# Sheet1.net
KiCad netlist of a schematic drawn in Altium Designer
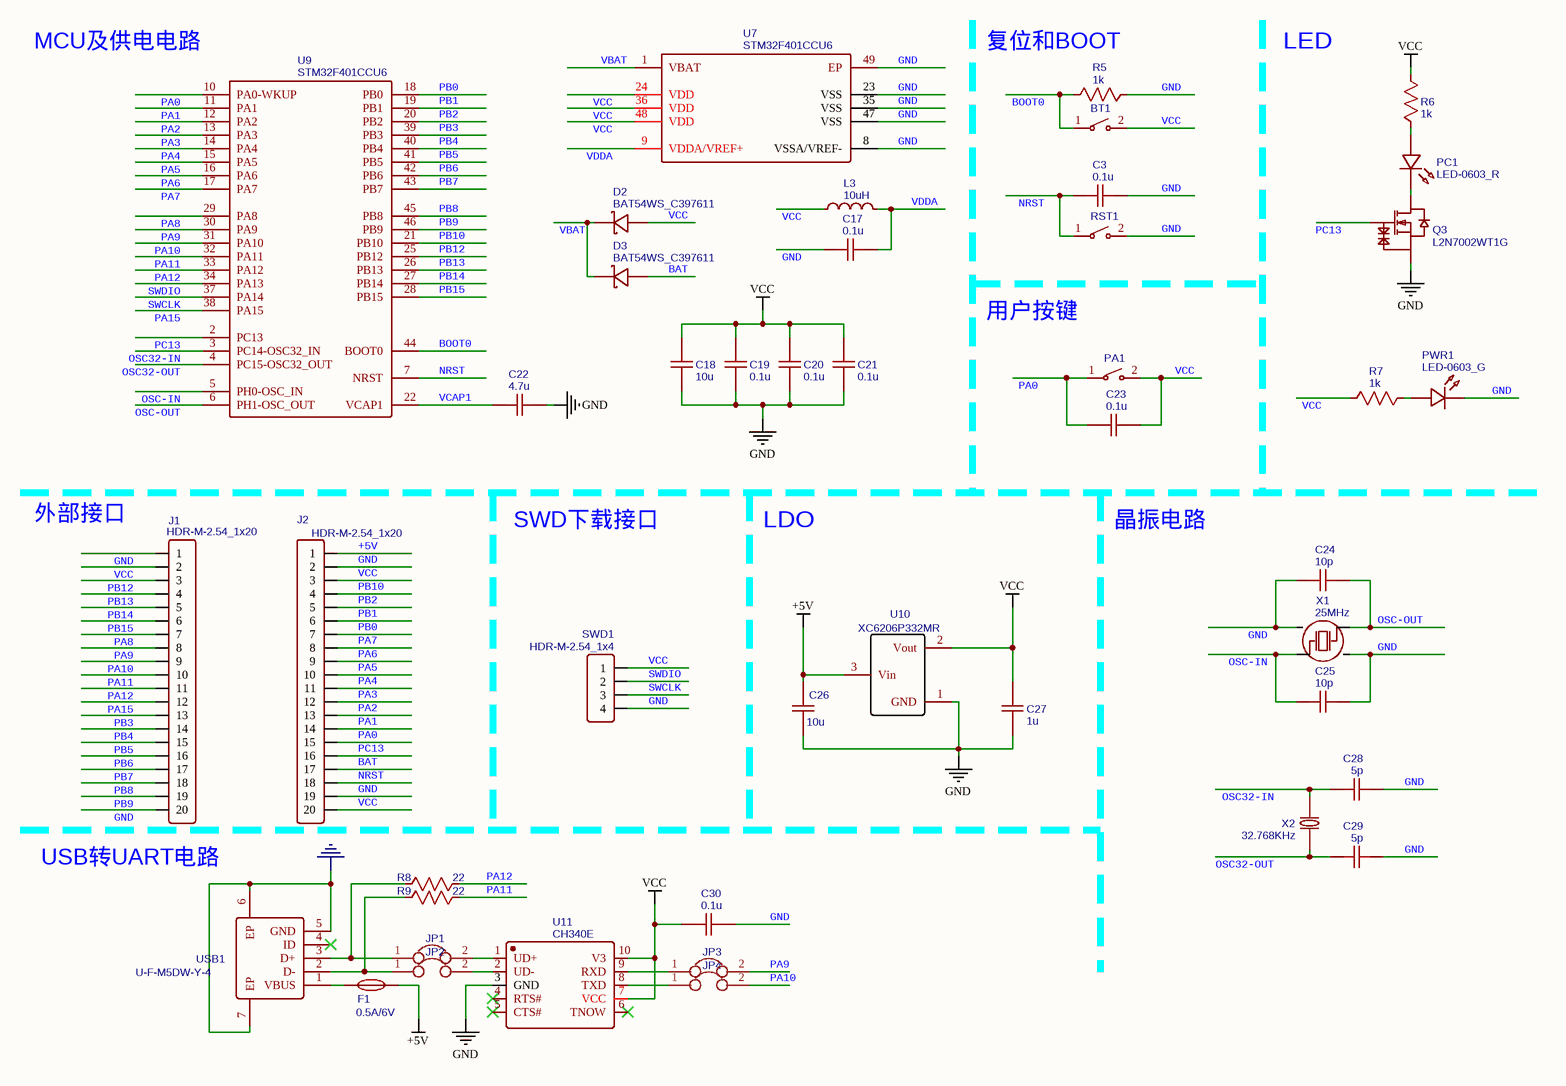
[diagram p0: Sheet1.SchDoc]

(export (version "E")
  (design (tool "Eeschema 10.0.6"))
  (components
    (comp (ref "BT1")
      (value "TS-1088R-02026")
      (footprint "SW-SMD_L3.9-W3.0-P4.45")
      (fields (field (name "BOM_SUPPLIER PART") "C455280") (field (name "CONTRIBUTOR") "LCSC"))
      (libsource (lib "altium-import") (part "root_0_TS-1088R-02026_"))
    )
    (comp (ref "C3")
      (value "0.1u")
      (footprint "0603")
      (fields (field (name "CONTRIBUTOR") "LCEDA_Lib"))
      (libsource (lib "altium-import") (part "root_2_0.1u_"))
    )
    (comp (ref "C17")
      (value "0.1u")
      (footprint "0603")
      (fields (field (name "CONTRIBUTOR") "LCEDA_Lib"))
      (libsource (lib "altium-import") (part "root_2_0.1u_"))
    )
    (comp (ref "C18")
      (value "10u")
      (footprint "0603")
      (fields (field (name "CONTRIBUTOR") "LCEDA_Lib"))
      (libsource (lib "altium-import") (part "root_1_10u_"))
    )
    (comp (ref "C19")
      (value "0.1u")
      (footprint "0603")
      (fields (field (name "CONTRIBUTOR") "LCEDA_Lib"))
      (libsource (lib "altium-import") (part "root_1_0.1u_"))
    )
    (comp (ref "C20")
      (value "0.1u")
      (footprint "0603")
      (fields (field (name "CONTRIBUTOR") "LCEDA_Lib"))
      (libsource (lib "altium-import") (part "root_1_0.1u_"))
    )
    (comp (ref "C21")
      (value "0.1u")
      (footprint "0603")
      (fields (field (name "CONTRIBUTOR") "LCEDA_Lib"))
      (libsource (lib "altium-import") (part "root_1_0.1u_"))
    )
    (comp (ref "C22")
      (value "4.7u")
      (footprint "0603")
      (fields (field (name "CONTRIBUTOR") "LCEDA_Lib"))
      (libsource (lib "altium-import") (part "root_0_4.7u_"))
    )
    (comp (ref "C23")
      (value "0.1u")
      (footprint "0603")
      (fields (field (name "CONTRIBUTOR") "LCEDA_Lib"))
      (libsource (lib "altium-import") (part "root_2_0.1u_"))
    )
    (comp (ref "C24")
      (value "10p")
      (footprint "0603")
      (fields (field (name "CONTRIBUTOR") "LCEDA_Lib"))
      (libsource (lib "altium-import") (part "root_0_10p_"))
    )
    (comp (ref "C25")
      (value "10p")
      (footprint "0603")
      (fields (field (name "CONTRIBUTOR") "LCEDA_Lib"))
      (libsource (lib "altium-import") (part "root_0_10p_"))
    )
    (comp (ref "C26") (value "10u") (footprint "0603") (libsource (lib "altium-import") (part "root_0_10u_")))
    (comp (ref "C27") (value "1u") (footprint "0603") (libsource (lib "altium-import") (part "root_0_1u_")))
    (comp (ref "C28")
      (value "5p")
      (footprint "0603")
      (fields (field (name "CONTRIBUTOR") "LCEDA_Lib"))
      (libsource (lib "altium-import") (part "root_0_5p_"))
    )
    (comp (ref "C29")
      (value "5p")
      (footprint "0603")
      (fields (field (name "CONTRIBUTOR") "LCEDA_Lib"))
      (libsource (lib "altium-import") (part "root_0_5p_"))
    )
    (comp (ref "C30") (value "0.1u") (footprint "0603") (libsource (lib "") (part "root_1_0.1u__1")))
    (comp (ref "D2")
      (value "BAT54WS_C397611")
      (fields
        (field (name "BOM_SUPPLIER PART") "C397611")
        (field (name "BOM_MANUFACTURER PART") "BAT54WS")
        (field (name "CONTRIBUTOR") "LCSC")
      )
      (libsource (lib "altium-import") (part "root_0_BAT54WS_C397611_"))
    )
    (comp (ref "D3")
      (value "BAT54WS_C397611")
      (fields
        (field (name "BOM_SUPPLIER PART") "C397611")
        (field (name "BOM_MANUFACTURER PART") "BAT54WS")
        (field (name "CONTRIBUTOR") "LCSC")
      )
      (libsource (lib "altium-import") (part "root_0_BAT54WS_C397611_"))
    )
    (comp (ref "F1")
      (value "0.5A/6V")
      (footprint "F0603")
      (fields
        (field (name "BOM_SUPPLIER PART") "C210357")
        (field (name "BOM_MANUFACTURER PART") "MF-FSMF050X-2")
        (field (name "CONTRIBUTOR") "LCSC")
      )
      (libsource (lib "altium-import") (part "root_0_0.5A/6V_"))
    )
    (comp (ref "J1")
      (value "HDR-M-2.54_1x20")
      (footprint "HDR-M-2.54_1X20")
      (fields (field (name "BOM_SUPPLIER PART") "C50981") (field (name "CONTRIBUTOR") "LCEDA_Lib"))
      (libsource (lib "") (part "root_0_HDR-M-2.54_1x20__1"))
    )
    (comp (ref "J2")
      (value "HDR-M-2.54_1x20")
      (footprint "HDR-M-2.54_1X20")
      (fields (field (name "BOM_SUPPLIER PART") "C50981") (field (name "CONTRIBUTOR") "LCEDA_Lib"))
      (libsource (lib "altium-import") (part "root_0_HDR-M-2.54_1x20_"))
    )
    (comp (ref "JP1")
      (value "JUMPER")
      (footprint "JUMPER-0603")
      (libsource (lib "altium-import") (part "root_0_JUMPER_"))
    )
    (comp (ref "JP2")
      (value "JUMPER")
      (footprint "JUMPER-0603")
      (libsource (lib "altium-import") (part "root_0_JUMPER_"))
    )
    (comp (ref "JP3")
      (value "JUMPER")
      (footprint "JUMPER-0603")
      (libsource (lib "altium-import") (part "root_0_JUMPER_"))
    )
    (comp (ref "JP4")
      (value "JUMPER")
      (footprint "JUMPER-0603")
      (libsource (lib "altium-import") (part "root_0_JUMPER_"))
    )
    (comp (ref "L3")
      (value "10uH")
      (footprint "L0805")
      (fields
        (field (name "BOM_SUPPLIER PART") "C281097")
        (field (name "BOM_MANUFACTURER PART") "MGFI2012D100KT-LF")
        (field (name "CONTRIBUTOR") "LCSC")
      )
      (libsource (lib "altium-import") (part "root_0_10uH_"))
    )
    (comp (ref "PA1")
      (value "TS-1088R-02026")
      (footprint "SW-SMD_L3.9-W3.0-P4.45")
      (fields (field (name "BOM_SUPPLIER PART") "C455280") (field (name "CONTRIBUTOR") "LCSC"))
      (libsource (lib "altium-import") (part "root_0_TS-1088R-02026_"))
    )
    (comp (ref "PC1")
      (value "LED-0603_R")
      (footprint "LED0603_RED")
      (fields
        (field (name "BOM_MANUFACTURER PART") "19-217/R6C-AL1M2VY/3T")
        (field (name "BOM_SUPPLIER PART") "C72044")
        (field (name "CONTRIBUTOR") "LCEDA_01")
      )
      (libsource (lib "altium-import") (part "root_3_LED-0603_R_"))
    )
    (comp (ref "PWR1")
      (value "LED-0603_G")
      (footprint "LED0603_GREEN")
      (fields
        (field (name "BOM_MANUFACTURER PART") "19-217/GHC-YR1S2/3T")
        (field (name "BOM_SUPPLIER PART") "C72043")
        (field (name "CONTRIBUTOR") "LCEDA_Lib")
      )
      (libsource (lib "altium-import") (part "root_0_LED-0603_G_"))
    )
    (comp (ref "Q3")
      (value "L2N7002WT1G")
      (footprint "SC-70-3_L2.1-W1.3-P1.30-LS2.1-BR")
      (fields (field (name "BOM_SUPPLIER PART") "C12778"))
      (libsource (lib "altium-import") (part "root_0_L2N7002WT1G_"))
    )
    (comp (ref "R5")
      (value "1k")
      (footprint "R0603")
      (fields (field (name "CONTRIBUTOR") "LCEDA_Lib"))
      (libsource (lib "altium-import") (part "root_0_1k_"))
    )
    (comp (ref "R6")
      (value "1k")
      (footprint "R0603")
      (fields (field (name "CONTRIBUTOR") "LCEDA_Lib"))
      (libsource (lib "altium-import") (part "root_1_1k_"))
    )
    (comp (ref "R7")
      (value "1k")
      (footprint "R0603")
      (fields (field (name "CONTRIBUTOR") "LCEDA_Lib"))
      (libsource (lib "altium-import") (part "root_2_1k_"))
    )
    (comp (ref "R8")
      (value "22")
      (footprint "R0603")
      (fields (field (name "CONTRIBUTOR") "LCEDA_Lib"))
      (libsource (lib "altium-import") (part "root_0_22_"))
    )
    (comp (ref "R9")
      (value "22")
      (footprint "R0603")
      (fields (field (name "CONTRIBUTOR") "LCEDA_Lib"))
      (libsource (lib "altium-import") (part "root_0_22_"))
    )
    (comp (ref "RST1")
      (value "TS-1088R-02026")
      (footprint "SW-SMD_L3.9-W3.0-P4.45")
      (fields (field (name "BOM_SUPPLIER PART") "C455280") (field (name "CONTRIBUTOR") "LCSC"))
      (libsource (lib "altium-import") (part "root_0_TS-1088R-02026_"))
    )
    (comp (ref "SWD1")
      (value "HDR-M-2.54_1x4")
      (footprint "HDR-M-2.54_1X4")
      (fields (field (name "BOM_SUPPLIER PART") "C124378") (field (name "CONTRIBUTOR") "LCEDA_Lib"))
      (libsource (lib "altium-import") (part "root_0_HDR-M-2.54_1x4_"))
    )
    (comp (ref "U7")
      (value "STM32F401CCU6")
      (footprint "UFQFPN-48_L7.0-W7.0-P0.50-BL-EP")
      (fields (field (name "BOM_SUPPLIER PART") "C79861") (field (name "SUBPART_NO") "1"))
      (libsource (lib "") (part "root_0_STM32F401CCU6__1"))
    )
    (comp (ref "U9")
      (value "STM32F401CCU6")
      (footprint "UFQFPN-48_L7.0-W7.0-P0.50-BL-EP")
      (fields (field (name "BOM_SUPPLIER PART") "C79861") (field (name "SUBPART_NO") "1"))
      (libsource (lib "altium-import") (part "root_0_STM32F401CCU6_"))
    )
    (comp (ref "U10")
      (value "XC6206P332MR")
      (footprint "SOT-23(SOT-23-3)")
      (fields (field (name "BOM_SUPPLIER PART") "C5446"))
      (libsource (lib "altium-import") (part "root_0_XC6206P332MR_"))
    )
    (comp (ref "U11")
      (value "CH340E")
      (footprint "MSOP-10_L3.0-W3.0-P0.50-LS5.0-BL")
      (fields (field (name "BOM_SUPPLIER PART") "C99652"))
      (libsource (lib "altium-import") (part "root_0_CH340E_"))
    )
    (comp (ref "USB1")
      (value "U-F-M5DW-Y-4")
      (footprint "MICRO-USB-A12")
      (fields (field (name "BOM_SUPPLIER PART") "C145784") (field (name "CONTRIBUTOR") "LCSC"))
      (libsource (lib "altium-import") (part "root_2_U-F-M5DW-Y-4_"))
    )
    (comp (ref "X1")
      (value "25MHz")
      (footprint "OSC-SMD_4P-L3.2-W2.5-BL")
      (fields
        (field (name "BOM_SUPPLIER PART") "C400090")
        (field (name "BOM_MANUFACTURER PART") "TAXM8M4RDBCCT2T")
        (field (name "CONTRIBUTOR") "LCSC")
      )
      (libsource (lib "altium-import") (part "root_0_25MHz_"))
    )
    (comp (ref "X2")
      (value "32.768KHz")
      (footprint "OSC-SMD_L3.2-W1.5")
      (fields
        (field (name "BOM_MANUFACTURER PART") "Q13FC1350004900")
        (field (name "BOM_SUPPLIER PART") "C95361")
      )
      (libsource (lib "altium-import") (part "root_1_32.768KHz_"))
    )
  )
  (nets
    (net (code "1") (name "+5V") (class "Default")
      (node (ref "C26") (pin "2") (pinfunction "2_2") (pintype "passive"))
      (node (ref "F1") (pin "2") (pinfunction "2_2") (pintype "passive"))
      (node (ref "J2") (pin "1") (pinfunction "1_1") (pintype "passive"))
      (node (ref "U10") (pin "3") (pinfunction "Vin_3") (pintype "passive"))
    )
    (net (code "2") (name "/BAT") (class "Default")
      (node (ref "D3") (pin "2") (pinfunction "A_2") (pintype "passive"))
      (node (ref "J2") (pin "17") (pinfunction "17_17") (pintype "passive"))
    )
    (net (code "3") (name "/BOOT0") (class "Default")
      (node (ref "BT1") (pin "1") (pinfunction "1_1") (pintype "passive"))
      (node (ref "R5") (pin "1") (pinfunction "1_1") (pintype "passive"))
      (node (ref "U9") (pin "44") (pinfunction "BOOT0_44") (pintype "passive"))
    )
    (net (code "4") (name "/NRST") (class "Default")
      (node (ref "C3") (pin "2") (pinfunction "2_2") (pintype "passive"))
      (node (ref "J2") (pin "18") (pinfunction "18_18") (pintype "passive"))
      (node (ref "RST1") (pin "1") (pinfunction "1_1") (pintype "passive"))
      (node (ref "U9") (pin "7") (pinfunction "NRST_7") (pintype "passive"))
    )
    (net (code "5") (name "/OSC-IN") (class "Default")
      (node (ref "C25") (pin "1") (pinfunction "1_1") (pintype "passive"))
      (node (ref "U9") (pin "5") (pinfunction "PH0-OSC_IN_5") (pintype "passive"))
      (node (ref "X1") (pin "1") (pinfunction "1_1") (pintype "passive"))
    )
    (net (code "6") (name "/OSC-OUT") (class "Default")
      (node (ref "C24") (pin "2") (pinfunction "2_2") (pintype "passive"))
      (node (ref "U9") (pin "6") (pinfunction "PH1-OSC_OUT_6") (pintype "passive"))
      (node (ref "X1") (pin "3") (pinfunction "3_3") (pintype "passive"))
    )
    (net (code "7") (name "/OSC32-IN") (class "Default")
      (node (ref "C28") (pin "2") (pinfunction "2_2") (pintype "passive"))
      (node (ref "U9") (pin "3") (pinfunction "PC14-OSC32_IN_3") (pintype "passive"))
      (node (ref "X2") (pin "2") (pinfunction "2_2") (pintype "passive"))
    )
    (net (code "8") (name "/OSC32-OUT") (class "Default")
      (node (ref "C29") (pin "2") (pinfunction "2_2") (pintype "passive"))
      (node (ref "U9") (pin "4") (pinfunction "PC15-OSC32_OUT_4") (pintype "passive"))
      (node (ref "X2") (pin "1") (pinfunction "1_1") (pintype "passive"))
    )
    (net (code "9") (name "/PA0") (class "Default")
      (node (ref "C23") (pin "2") (pinfunction "2_2") (pintype "passive"))
      (node (ref "J2") (pin "15") (pinfunction "15_15") (pintype "passive"))
      (node (ref "PA1") (pin "1") (pinfunction "1_1") (pintype "passive"))
      (node (ref "U9") (pin "10") (pinfunction "PA0-WKUP_10") (pintype "passive"))
    )
    (net (code "10") (name "/PA1") (class "Default")
      (node (ref "J2") (pin "14") (pinfunction "14_14") (pintype "passive"))
      (node (ref "U9") (pin "11") (pinfunction "PA1_11") (pintype "passive"))
    )
    (net (code "11") (name "/PA2") (class "Default")
      (node (ref "J2") (pin "13") (pinfunction "13_13") (pintype "passive"))
      (node (ref "U9") (pin "12") (pinfunction "PA2_12") (pintype "passive"))
    )
    (net (code "12") (name "/PA3") (class "Default")
      (node (ref "J2") (pin "12") (pinfunction "12_12") (pintype "passive"))
      (node (ref "U9") (pin "13") (pinfunction "PA3_13") (pintype "passive"))
    )
    (net (code "13") (name "/PA4") (class "Default")
      (node (ref "J2") (pin "11") (pinfunction "11_11") (pintype "passive"))
      (node (ref "U9") (pin "14") (pinfunction "PA4_14") (pintype "passive"))
    )
    (net (code "14") (name "/PA5") (class "Default")
      (node (ref "J2") (pin "10") (pinfunction "10_10") (pintype "passive"))
      (node (ref "U9") (pin "15") (pinfunction "PA5_15") (pintype "passive"))
    )
    (net (code "15") (name "/PA6") (class "Default")
      (node (ref "J2") (pin "9") (pinfunction "9_9") (pintype "passive"))
      (node (ref "U9") (pin "16") (pinfunction "PA6_16") (pintype "passive"))
    )
    (net (code "16") (name "/PA7") (class "Default")
      (node (ref "J2") (pin "8") (pinfunction "8_8") (pintype "passive"))
      (node (ref "U9") (pin "17") (pinfunction "PA7_17") (pintype "passive"))
    )
    (net (code "17") (name "/PA8") (class "Default")
      (node (ref "J1") (pin "7") (pinfunction "7_7") (pintype "passive"))
      (node (ref "U9") (pin "29") (pinfunction "PA8_29") (pintype "passive"))
    )
    (net (code "18") (name "/PA9") (class "Default")
      (node (ref "J1") (pin "8") (pinfunction "8_8") (pintype "passive"))
      (node (ref "JP3") (pin "2") (pinfunction "2_2") (pintype "passive"))
      (node (ref "U9") (pin "30") (pinfunction "PA9_30") (pintype "passive"))
    )
    (net (code "19") (name "/PA10") (class "Default")
      (node (ref "J1") (pin "9") (pinfunction "9_9") (pintype "passive"))
      (node (ref "JP4") (pin "2") (pinfunction "2_2") (pintype "passive"))
      (node (ref "U9") (pin "31") (pinfunction "PA10_31") (pintype "passive"))
    )
    (net (code "20") (name "/PA11") (class "Default")
      (node (ref "J1") (pin "10") (pinfunction "10_10") (pintype "passive"))
      (node (ref "R9") (pin "2") (pinfunction "2_2") (pintype "passive"))
      (node (ref "U9") (pin "32") (pinfunction "PA11_32") (pintype "passive"))
    )
    (net (code "21") (name "/PA12") (class "Default")
      (node (ref "J1") (pin "11") (pinfunction "11_11") (pintype "passive"))
      (node (ref "R8") (pin "2") (pinfunction "2_2") (pintype "passive"))
      (node (ref "U9") (pin "33") (pinfunction "PA12_33") (pintype "passive"))
    )
    (net (code "22") (name "/PA15") (class "Default")
      (node (ref "J1") (pin "12") (pinfunction "12_12") (pintype "passive"))
      (node (ref "U9") (pin "38") (pinfunction "PA15_38") (pintype "passive"))
    )
    (net (code "23") (name "/PB0") (class "Default")
      (node (ref "J2") (pin "7") (pinfunction "7_7") (pintype "passive"))
      (node (ref "U9") (pin "18") (pinfunction "PB0_18") (pintype "passive"))
    )
    (net (code "24") (name "/PB1") (class "Default")
      (node (ref "J2") (pin "6") (pinfunction "6_6") (pintype "passive"))
      (node (ref "U9") (pin "19") (pinfunction "PB1_19") (pintype "passive"))
    )
    (net (code "25") (name "/PB2") (class "Default")
      (node (ref "J2") (pin "5") (pinfunction "5_5") (pintype "passive"))
      (node (ref "U9") (pin "20") (pinfunction "PB2_20") (pintype "passive"))
    )
    (net (code "26") (name "/PB3") (class "Default")
      (node (ref "J1") (pin "13") (pinfunction "13_13") (pintype "passive"))
      (node (ref "U9") (pin "39") (pinfunction "PB3_39") (pintype "passive"))
    )
    (net (code "27") (name "/PB4") (class "Default")
      (node (ref "J1") (pin "14") (pinfunction "14_14") (pintype "passive"))
      (node (ref "U9") (pin "40") (pinfunction "PB4_40") (pintype "passive"))
    )
    (net (code "28") (name "/PB5") (class "Default")
      (node (ref "J1") (pin "15") (pinfunction "15_15") (pintype "passive"))
      (node (ref "U9") (pin "41") (pinfunction "PB5_41") (pintype "passive"))
    )
    (net (code "29") (name "/PB6") (class "Default")
      (node (ref "J1") (pin "16") (pinfunction "16_16") (pintype "passive"))
      (node (ref "U9") (pin "42") (pinfunction "PB6_42") (pintype "passive"))
    )
    (net (code "30") (name "/PB7") (class "Default")
      (node (ref "J1") (pin "17") (pinfunction "17_17") (pintype "passive"))
      (node (ref "U9") (pin "43") (pinfunction "PB7_43") (pintype "passive"))
    )
    (net (code "31") (name "/PB8") (class "Default")
      (node (ref "J1") (pin "18") (pinfunction "18_18") (pintype "passive"))
      (node (ref "U9") (pin "45") (pinfunction "PB8_45") (pintype "passive"))
    )
    (net (code "32") (name "/PB9") (class "Default")
      (node (ref "J1") (pin "19") (pinfunction "19_19") (pintype "passive"))
      (node (ref "U9") (pin "46") (pinfunction "PB9_46") (pintype "passive"))
    )
    (net (code "33") (name "/PB10") (class "Default")
      (node (ref "J2") (pin "4") (pinfunction "4_4") (pintype "passive"))
      (node (ref "U9") (pin "21") (pinfunction "PB10_21") (pintype "passive"))
    )
    (net (code "34") (name "/PB12") (class "Default")
      (node (ref "J1") (pin "3") (pinfunction "3_3") (pintype "passive"))
      (node (ref "U9") (pin "25") (pinfunction "PB12_25") (pintype "passive"))
    )
    (net (code "35") (name "/PB13") (class "Default")
      (node (ref "J1") (pin "4") (pinfunction "4_4") (pintype "passive"))
      (node (ref "U9") (pin "26") (pinfunction "PB13_26") (pintype "passive"))
    )
    (net (code "36") (name "/PB14") (class "Default")
      (node (ref "J1") (pin "5") (pinfunction "5_5") (pintype "passive"))
      (node (ref "U9") (pin "27") (pinfunction "PB14_27") (pintype "passive"))
    )
    (net (code "37") (name "/PB15") (class "Default")
      (node (ref "J1") (pin "6") (pinfunction "6_6") (pintype "passive"))
      (node (ref "U9") (pin "28") (pinfunction "PB15_28") (pintype "passive"))
    )
    (net (code "38") (name "/PC13") (class "Default")
      (node (ref "J2") (pin "16") (pinfunction "16_16") (pintype "passive"))
      (node (ref "Q3") (pin "1") (pinfunction "G_1") (pintype "passive"))
      (node (ref "U9") (pin "2") (pinfunction "PC13_2") (pintype "passive"))
    )
    (net (code "39") (name "/SWCLK") (class "Default")
      (node (ref "SWD1") (pin "3") (pinfunction "3_3") (pintype "passive"))
      (node (ref "U9") (pin "37") (pinfunction "PA14_37") (pintype "passive"))
    )
    (net (code "40") (name "/SWDIO") (class "Default")
      (node (ref "SWD1") (pin "2") (pinfunction "2_2") (pintype "passive"))
      (node (ref "U9") (pin "34") (pinfunction "PA13_34") (pintype "passive"))
    )
    (net (code "41") (name "/VBAT") (class "Default")
      (node (ref "D2") (pin "1") (pinfunction "C_1") (pintype "passive"))
      (node (ref "D3") (pin "1") (pinfunction "C_1") (pintype "passive"))
      (node (ref "U7") (pin "1") (pinfunction "VBAT_1") (pintype "passive"))
    )
    (net (code "42") (name "/VCAP1") (class "Default")
      (node (ref "C22") (pin "1") (pinfunction "1_1") (pintype "passive"))
      (node (ref "U9") (pin "22") (pinfunction "VCAP1_22") (pintype "passive"))
    )
    (net (code "43") (name "/VDDA") (class "Default")
      (node (ref "C17") (pin "1") (pinfunction "1_1") (pintype "passive"))
      (node (ref "L3") (pin "2") (pinfunction "2_2") (pintype "passive"))
      (node (ref "U7") (pin "9") (pinfunction "VDDA/VREF+_9") (pintype "passive"))
    )
    (net (code "44") (name "GND") (class "Default")
      (node (ref "C17") (pin "2") (pinfunction "2_2") (pintype "passive"))
      (node (ref "C18") (pin "1") (pinfunction "1_1") (pintype "passive"))
      (node (ref "C19") (pin "1") (pinfunction "1_1") (pintype "passive"))
      (node (ref "C20") (pin "1") (pinfunction "1_1") (pintype "passive"))
      (node (ref "C21") (pin "1") (pinfunction "1_1") (pintype "passive"))
      (node (ref "C22") (pin "2") (pinfunction "2_2") (pintype "passive"))
      (node (ref "C24") (pin "1") (pinfunction "1_1") (pintype "passive"))
      (node (ref "C25") (pin "2") (pinfunction "2_2") (pintype "passive"))
      (node (ref "C26") (pin "1") (pinfunction "1_1") (pintype "passive"))
      (node (ref "C27") (pin "1") (pinfunction "1_1") (pintype "passive"))
      (node (ref "C28") (pin "1") (pinfunction "1_1") (pintype "passive"))
      (node (ref "C29") (pin "1") (pinfunction "1_1") (pintype "passive"))
      (node (ref "C3") (pin "1") (pinfunction "1_1") (pintype "passive"))
      (node (ref "C30") (pin "1") (pinfunction "1_1") (pintype "passive"))
      (node (ref "J1") (pin "1") (pinfunction "1_1") (pintype "passive"))
      (node (ref "J1") (pin "20") (pinfunction "20_20") (pintype "passive"))
      (node (ref "J2") (pin "19") (pinfunction "19_19") (pintype "passive"))
      (node (ref "J2") (pin "2") (pinfunction "2_2") (pintype "passive"))
      (node (ref "PWR1") (pin "2") (pinfunction "2_2") (pintype "passive"))
      (node (ref "Q3") (pin "2") (pinfunction "S_2") (pintype "passive"))
      (node (ref "R5") (pin "2") (pinfunction "2_2") (pintype "passive"))
      (node (ref "RST1") (pin "2") (pinfunction "2_2") (pintype "passive"))
      (node (ref "SWD1") (pin "4") (pinfunction "4_4") (pintype "passive"))
      (node (ref "U10") (pin "1") (pinfunction "GND_1") (pintype "passive"))
      (node (ref "U11") (pin "3") (pinfunction "GND_3") (pintype "passive"))
      (node (ref "U7") (pin "23") (pinfunction "VSS_23") (pintype "passive"))
      (node (ref "U7") (pin "35") (pinfunction "VSS_35") (pintype "passive"))
      (node (ref "U7") (pin "47") (pinfunction "VSS_47") (pintype "passive"))
      (node (ref "U7") (pin "49") (pinfunction "EP_49") (pintype "passive"))
      (node (ref "U7") (pin "8") (pinfunction "VSSA/VREF-_8") (pintype "passive"))
      (node (ref "USB1") (pin "5") (pinfunction "GND_5") (pintype "passive"))
      (node (ref "USB1") (pin "6") (pinfunction "EP_6") (pintype "passive"))
      (node (ref "USB1") (pin "7") (pinfunction "EP_7") (pintype "passive"))
      (node (ref "X1") (pin "2") (pinfunction "2_2") (pintype "passive"))
      (node (ref "X1") (pin "4") (pinfunction "4_4") (pintype "passive"))
    )
    (net (code "45") (name "Net-(PC1-Pad1)") (class "Default")
      (node (ref "PC1") (pin "1") (pinfunction "1_1") (pintype "passive"))
      (node (ref "R6") (pin "1") (pinfunction "1_1") (pintype "passive"))
    )
    (net (code "46") (name "Net-(PWR1-Pad1)") (class "Default")
      (node (ref "PWR1") (pin "1") (pinfunction "1_1") (pintype "passive"))
      (node (ref "R7") (pin "1") (pinfunction "1_1") (pintype "passive"))
    )
    (net (code "47") (name "Net-(Q3-D)") (class "Default")
      (node (ref "PC1") (pin "2") (pinfunction "2_2") (pintype "passive"))
      (node (ref "Q3") (pin "3") (pinfunction "D_3") (pintype "passive"))
    )
    (net (code "48") (name "Net-(U11-RXD)") (class "Default")
      (node (ref "JP3") (pin "1") (pinfunction "1_1") (pintype "passive"))
      (node (ref "U11") (pin "9") (pinfunction "RXD_9") (pintype "passive"))
    )
    (net (code "49") (name "Net-(U11-TXD)") (class "Default")
      (node (ref "JP4") (pin "1") (pinfunction "1_1") (pintype "passive"))
      (node (ref "U11") (pin "8") (pinfunction "TXD_8") (pintype "passive"))
    )
    (net (code "50") (name "Net-(U11-UD+)") (class "Default")
      (node (ref "JP1") (pin "2") (pinfunction "2_2") (pintype "passive"))
      (node (ref "U11") (pin "1") (pinfunction "UD+_1") (pintype "passive"))
    )
    (net (code "51") (name "Net-(U11-UD-)") (class "Default")
      (node (ref "JP2") (pin "2") (pinfunction "2_2") (pintype "passive"))
      (node (ref "U11") (pin "2") (pinfunction "UD-_2") (pintype "passive"))
    )
    (net (code "52") (name "Net-(USB1-D+)") (class "Default")
      (node (ref "JP1") (pin "1") (pinfunction "1_1") (pintype "passive"))
      (node (ref "R8") (pin "1") (pinfunction "1_1") (pintype "passive"))
      (node (ref "USB1") (pin "3") (pinfunction "D+_3") (pintype "passive"))
    )
    (net (code "53") (name "Net-(USB1-D-)") (class "Default")
      (node (ref "JP2") (pin "1") (pinfunction "1_1") (pintype "passive"))
      (node (ref "R9") (pin "1") (pinfunction "1_1") (pintype "passive"))
      (node (ref "USB1") (pin "2") (pinfunction "D-_2") (pintype "passive"))
    )
    (net (code "54") (name "Net-(USB1-VBUS)") (class "Default")
      (node (ref "F1") (pin "1") (pinfunction "1_1") (pintype "passive"))
      (node (ref "USB1") (pin "1") (pinfunction "VBUS_1") (pintype "passive"))
    )
    (net (code "55") (name "VCC") (class "Default")
      (node (ref "BT1") (pin "2") (pinfunction "2_2") (pintype "passive"))
      (node (ref "C18") (pin "2") (pinfunction "2_2") (pintype "passive"))
      (node (ref "C19") (pin "2") (pinfunction "2_2") (pintype "passive"))
      (node (ref "C20") (pin "2") (pinfunction "2_2") (pintype "passive"))
      (node (ref "C21") (pin "2") (pinfunction "2_2") (pintype "passive"))
      (node (ref "C23") (pin "1") (pinfunction "1_1") (pintype "passive"))
      (node (ref "C27") (pin "2") (pinfunction "2_2") (pintype "passive"))
      (node (ref "C30") (pin "2") (pinfunction "2_2") (pintype "passive"))
      (node (ref "D2") (pin "2") (pinfunction "A_2") (pintype "passive"))
      (node (ref "J1") (pin "2") (pinfunction "2_2") (pintype "passive"))
      (node (ref "J2") (pin "20") (pinfunction "20_20") (pintype "passive"))
      (node (ref "J2") (pin "3") (pinfunction "3_3") (pintype "passive"))
      (node (ref "L3") (pin "1") (pinfunction "1_1") (pintype "passive"))
      (node (ref "PA1") (pin "2") (pinfunction "2_2") (pintype "passive"))
      (node (ref "R6") (pin "2") (pinfunction "2_2") (pintype "passive"))
      (node (ref "R7") (pin "2") (pinfunction "2_2") (pintype "passive"))
      (node (ref "SWD1") (pin "1") (pinfunction "1_1") (pintype "passive"))
      (node (ref "U10") (pin "2") (pinfunction "Vout_2") (pintype "passive"))
      (node (ref "U11") (pin "10") (pinfunction "V3_10") (pintype "passive"))
      (node (ref "U11") (pin "7") (pinfunction "VCC_7") (pintype "passive"))
      (node (ref "U7") (pin "24") (pinfunction "VDD_24") (pintype "passive"))
      (node (ref "U7") (pin "36") (pinfunction "VDD_36") (pintype "passive"))
      (node (ref "U7") (pin "48") (pinfunction "VDD_48") (pintype "passive"))
    )
    (net (code "56") (name "unconnected-(U11-CTS#-Pad5)") (class "Default")
      (node (ref "U11") (pin "5") (pinfunction "CTS#_5") (pintype "passive+no_connect"))
    )
    (net (code "57") (name "unconnected-(U11-RTS#-Pad4)") (class "Default")
      (node (ref "U11") (pin "4") (pinfunction "RTS#_4") (pintype "passive+no_connect"))
    )
    (net (code "58") (name "unconnected-(U11-TNOW-Pad6)") (class "Default")
      (node (ref "U11") (pin "6") (pinfunction "TNOW_6") (pintype "passive+no_connect"))
    )
    (net (code "59") (name "unconnected-(USB1-ID-Pad4)") (class "Default")
      (node (ref "USB1") (pin "4") (pinfunction "ID_4") (pintype "passive+no_connect"))
    )
  )
)
